# 8_DBUS_schdoc.net
KiCad netlist of a schematic drawn in Altium Designer
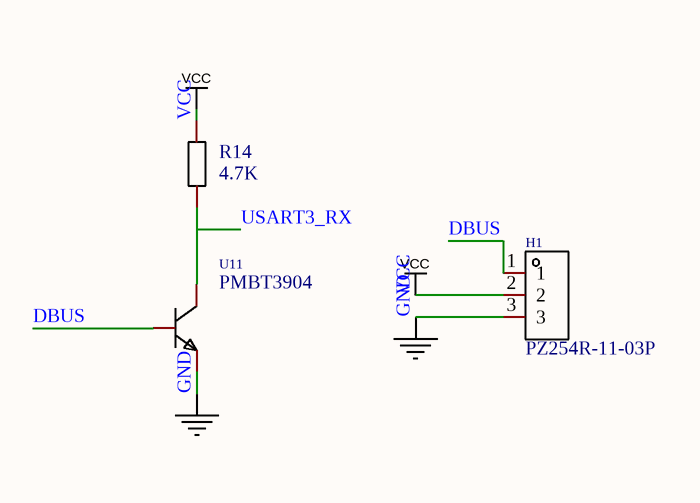
[diagram p0: 8_DBUS.schdoc.schdoc]

(export (version "E")
  (design (tool "Eeschema 10.0.6"))
  (components
    (comp (ref "H1")
      (value "PZ254R-11-03P")
      (fields (field (name "NAME") "PZ254R-11-03P") (field (name "MANUFACTURER") "XFCN(兴飞)"))
      (libsource (lib "altium-import") (part "root_0_PZ254R-11-03P_"))
    )
    (comp (ref "R14")
      (value "4.7K")
      (fields (field (name "NAME") "4.7K"))
      (libsource (lib "altium-import") (part "root_3_Res_0603_"))
    )
    (comp (ref "U11")
      (value "PMBT3904")
      (fields (field (name "NAME") "PMBT3904") (field (name "MANUFACTURER") "PAKER(派克微)"))
      (libsource (lib "altium-import") (part "root_0_PMBT3904_"))
    )
  )
  (nets
    (net (code "1") (name "/DBUS") (class "Default")
      (node (ref "H1") (pin "1") (pinfunction "1_1") (pintype "passive"))
      (node (ref "U11") (pin "1") (pinfunction "B_1") (pintype "passive"))
    )
    (net (code "2") (name "/GND") (class "Default")
      (node (ref "H1") (pin "3") (pinfunction "3_3") (pintype "passive"))
      (node (ref "U11") (pin "2") (pinfunction "E_2") (pintype "passive"))
    )
    (net (code "3") (name "/USART3_RX") (class "Default")
      (node (ref "R14") (pin "2") (pinfunction "2_2") (pintype "passive"))
      (node (ref "U11") (pin "3") (pinfunction "C_3") (pintype "passive"))
    )
    (net (code "4") (name "VCC") (class "Default")
      (node (ref "H1") (pin "2") (pinfunction "2_2") (pintype "passive"))
      (node (ref "R14") (pin "1") (pinfunction "1_1") (pintype "passive"))
    )
  )
)
